# v1.net
KiCad netlist of a schematic drawn in EAGLE
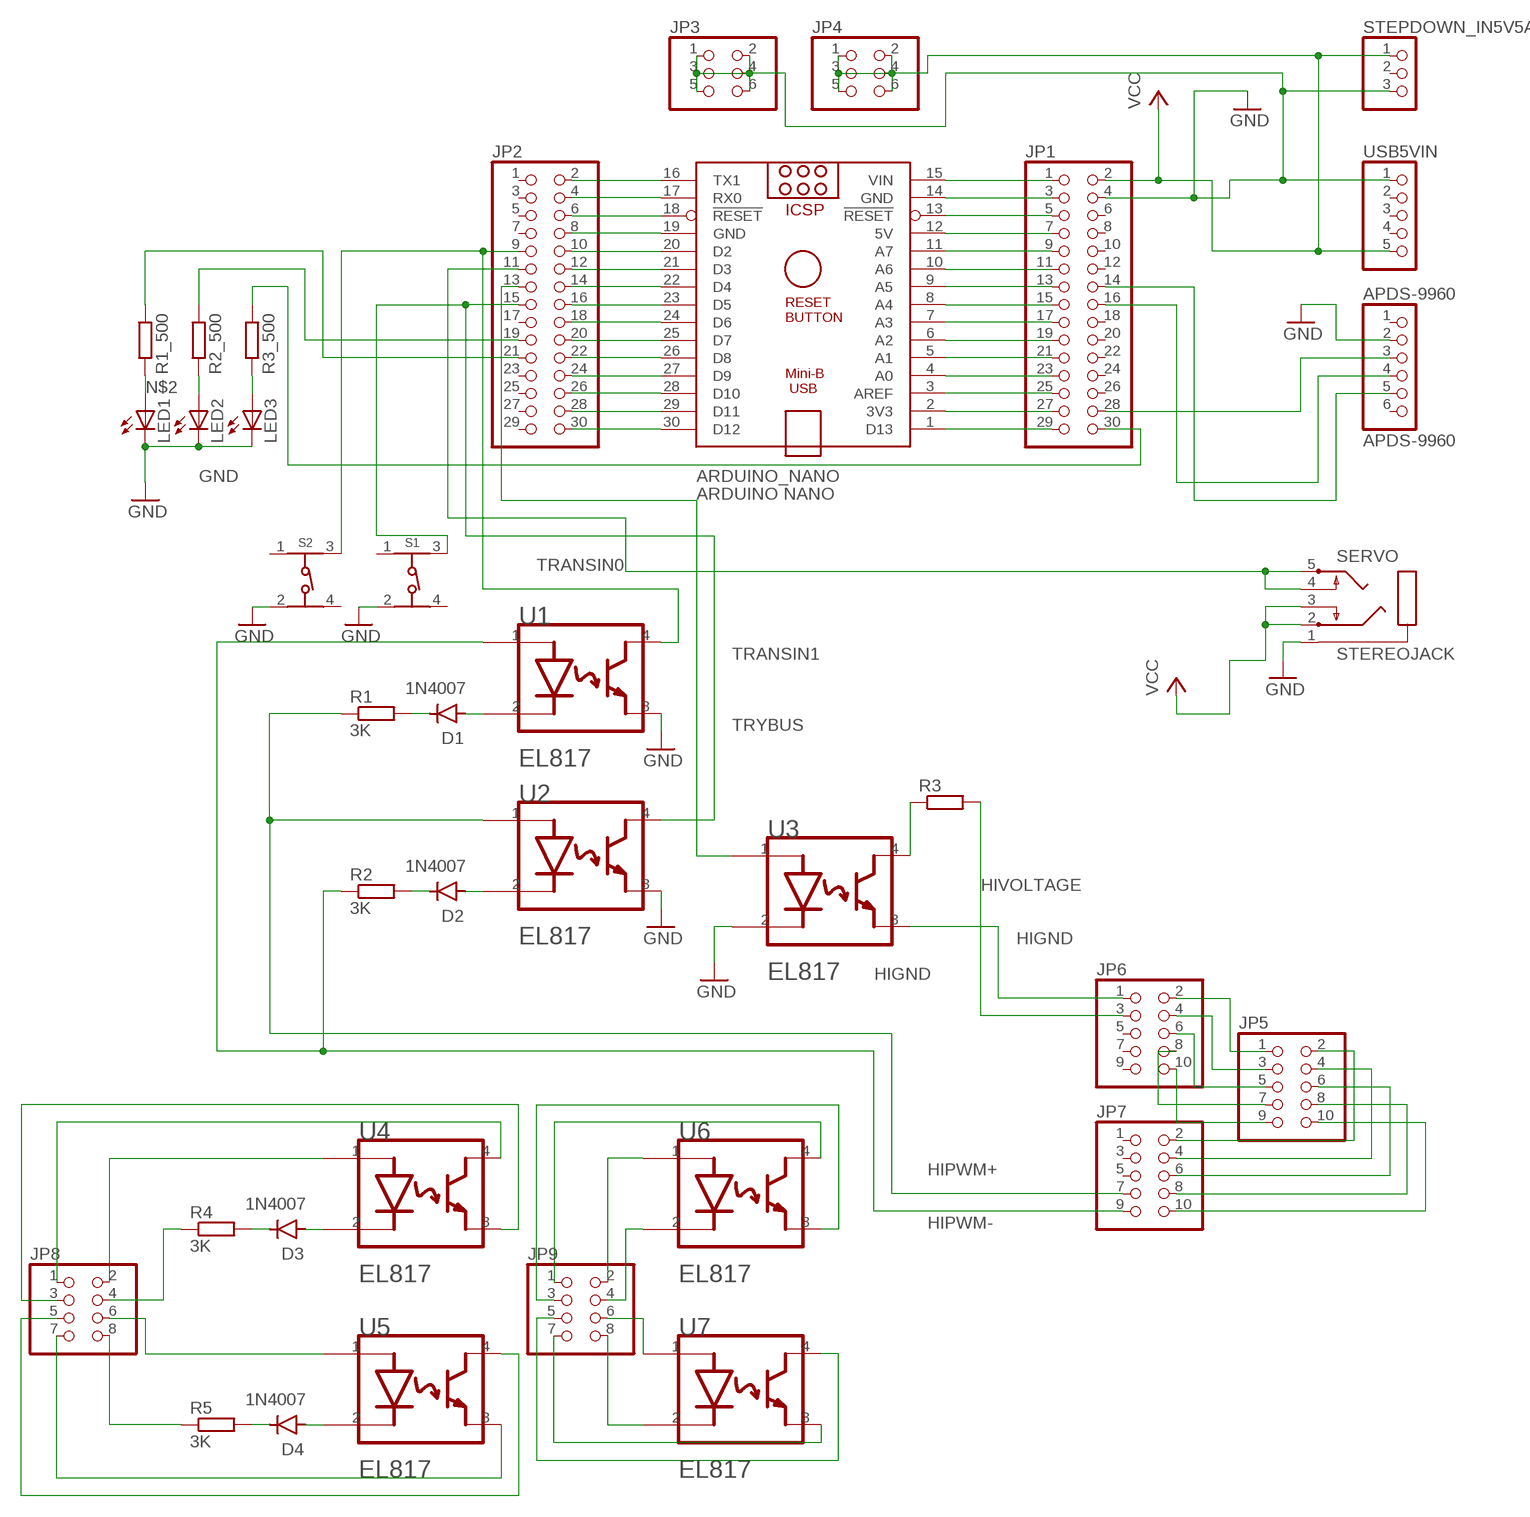
[diagram p0: schematic, sheet 1]

(export (version "E")
  (design (tool "Eeschema 10.0.6"))
  (components
    (comp (ref "APDS-9960")
      (value "APDS-9960")
      (footprint "eagle-import:1X06")
      (libsource (lib "eagle-import") (part "PINHD-1X6"))
    )
    (comp (ref "ARDUINO_NANO")
      (value "ARDUINO NANO")
      (footprint "eagle-import:ARDUINO_NANO")
      (libsource (lib "eagle-import") (part "ARDUINO_NANO"))
    )
    (comp (ref "D1")
      (value "1N4007")
      (footprint "eagle-import:DO-41")
      (fields
        (field (name "DIGIKEY_PART_NUMBER") "1N4007MSCT-ND")
        (field (name "MANUFACTURER") "Micro Commercial Co")
        (field (name "CREATED_BY") "PCBLayout.com")
      )
      (libsource (lib "eagle-import") (part "1N4007"))
    )
    (comp (ref "D2")
      (value "1N4007")
      (footprint "eagle-import:DO-41")
      (fields
        (field (name "DIGIKEY_PART_NUMBER") "1N4007MSCT-ND")
        (field (name "MANUFACTURER") "Micro Commercial Co")
        (field (name "CREATED_BY") "PCBLayout.com")
      )
      (libsource (lib "eagle-import") (part "1N4007"))
    )
    (comp (ref "D3")
      (value "1N4007")
      (footprint "eagle-import:DO-41")
      (fields
        (field (name "DIGIKEY_PART_NUMBER") "1N4007MSCT-ND")
        (field (name "MANUFACTURER") "Micro Commercial Co")
        (field (name "CREATED_BY") "PCBLayout.com")
      )
      (libsource (lib "eagle-import") (part "1N4007"))
    )
    (comp (ref "D4")
      (value "1N4007")
      (footprint "eagle-import:DO-41")
      (fields
        (field (name "DIGIKEY_PART_NUMBER") "1N4007MSCT-ND")
        (field (name "MANUFACTURER") "Micro Commercial Co")
        (field (name "CREATED_BY") "PCBLayout.com")
      )
      (libsource (lib "eagle-import") (part "1N4007"))
    )
    (comp (ref "JP1")
      (value "PINHD-2X15")
      (footprint "eagle-import:2X15")
      (libsource (lib "eagle-import") (part "PINHD-2X15"))
    )
    (comp (ref "JP2")
      (value "PINHD-2X15")
      (footprint "eagle-import:2X15")
      (libsource (lib "eagle-import") (part "PINHD-2X15"))
    )
    (comp (ref "JP3")
      (value "PINHD-2X3")
      (footprint "eagle-import:2X03")
      (libsource (lib "eagle-import") (part "PINHD-2X3"))
    )
    (comp (ref "JP4")
      (value "PINHD-2X3")
      (footprint "eagle-import:2X03")
      (libsource (lib "eagle-import") (part "PINHD-2X3"))
    )
    (comp (ref "JP5")
      (value "PINHD-2X5")
      (footprint "eagle-import:2X05")
      (libsource (lib "eagle-import") (part "PINHD-2X5"))
    )
    (comp (ref "JP6")
      (value "PINHD-2X5")
      (footprint "eagle-import:2X05")
      (libsource (lib "eagle-import") (part "PINHD-2X5"))
    )
    (comp (ref "JP7")
      (value "PINHD-2X5")
      (footprint "eagle-import:2X05")
      (libsource (lib "eagle-import") (part "PINHD-2X5"))
    )
    (comp (ref "JP8")
      (value "PINHD-2X4")
      (footprint "eagle-import:2X04")
      (libsource (lib "eagle-import") (part "PINHD-2X4"))
    )
    (comp (ref "JP9")
      (value "PINHD-2X4")
      (footprint "eagle-import:2X04")
      (libsource (lib "eagle-import") (part "PINHD-2X4"))
    )
    (comp (ref "LED1")
      (value "LED3MM")
      (footprint "eagle-import:LED3MM")
      (libsource (lib "eagle-import") (part "LED3MM"))
    )
    (comp (ref "LED2")
      (value "LED3MM")
      (footprint "eagle-import:LED3MM")
      (libsource (lib "eagle-import") (part "LED3MM"))
    )
    (comp (ref "LED3")
      (value "LED3MM")
      (footprint "eagle-import:LED3MM")
      (libsource (lib "eagle-import") (part "LED3MM"))
    )
    (comp (ref "R1")
      (value "3K")
      (footprint "eagle-import:0207_10")
      (libsource (lib "eagle-import") (part "R-EU_0207/10"))
    )
    (comp (ref "R1_500")
      (value "R-EU_0207/10")
      (footprint "eagle-import:0207_10")
      (libsource (lib "eagle-import") (part "R-EU_0207/10"))
    )
    (comp (ref "R2")
      (value "3K")
      (footprint "eagle-import:0207_10")
      (libsource (lib "eagle-import") (part "R-EU_0207/10"))
    )
    (comp (ref "R2_500")
      (value "R-EU_0207/10")
      (footprint "eagle-import:0207_10")
      (libsource (lib "eagle-import") (part "R-EU_0207/10"))
    )
    (comp (ref "R3")
      (value "R-EU_0207/10")
      (footprint "eagle-import:0207_10")
      (libsource (lib "eagle-import") (part "R-EU_0207/10"))
    )
    (comp (ref "R3_500")
      (value "R-EU_0207/10")
      (footprint "eagle-import:0207_10")
      (libsource (lib "eagle-import") (part "R-EU_0207/10"))
    )
    (comp (ref "R4")
      (value "3K")
      (footprint "eagle-import:0207_10")
      (libsource (lib "eagle-import") (part "R-EU_0207/10"))
    )
    (comp (ref "R5")
      (value "3K")
      (footprint "eagle-import:0207_10")
      (libsource (lib "eagle-import") (part "R-EU_0207/10"))
    )
    (comp (ref "S1")
      (value "430156070726")
      (footprint "eagle-import:4301X60707X6")
      (libsource (lib "eagle-import") (part "430156070726"))
    )
    (comp (ref "S2")
      (value "430156070726")
      (footprint "eagle-import:4301X60707X6")
      (libsource (lib "eagle-import") (part "430156070726"))
    )
    (comp (ref "SERVO")
      (value "STEREOJACK")
      (footprint "eagle-import:STX3100")
      (libsource (lib "eagle-import") (part "STEREOJACK"))
    )
    (comp (ref "STEPDOWN_IN5V5A")
      (value "PINHD-1X3")
      (footprint "eagle-import:1X03")
      (libsource (lib "eagle-import") (part "PINHD-1X3"))
    )
    (comp (ref "U1")
      (value "EVERLIGHT_EL817EVERLIGHT_EL817_0_0")
      (footprint "eagle-import:EVERLIGHT_EL817_0")
      (fields
        (field (name "DIGIKEY_PART_NUMBER") "EL817-ND")
        (field (name "MF") "Everlight")
        (field (name "MOUSER_PART_NUMBER") "638-817")
      )
      (libsource (lib "eagle-import") (part "EVERLIGHT_EL817EVERLIGHT_EL817_0_0"))
    )
    (comp (ref "U2")
      (value "EVERLIGHT_EL817EVERLIGHT_EL817_0_0")
      (footprint "eagle-import:EVERLIGHT_EL817_0")
      (fields
        (field (name "DIGIKEY_PART_NUMBER") "EL817-ND")
        (field (name "MF") "Everlight")
        (field (name "MOUSER_PART_NUMBER") "638-817")
      )
      (libsource (lib "eagle-import") (part "EVERLIGHT_EL817EVERLIGHT_EL817_0_0"))
    )
    (comp (ref "U3")
      (value "EVERLIGHT_EL817EVERLIGHT_EL817_0_0")
      (footprint "eagle-import:EVERLIGHT_EL817_0")
      (fields
        (field (name "DIGIKEY_PART_NUMBER") "EL817-ND")
        (field (name "MF") "Everlight")
        (field (name "MOUSER_PART_NUMBER") "638-817")
      )
      (libsource (lib "eagle-import") (part "EVERLIGHT_EL817EVERLIGHT_EL817_0_0"))
    )
    (comp (ref "U4")
      (value "EVERLIGHT_EL817EVERLIGHT_EL817_0_0")
      (footprint "eagle-import:EVERLIGHT_EL817_0")
      (fields
        (field (name "DIGIKEY_PART_NUMBER") "EL817-ND")
        (field (name "MF") "Everlight")
        (field (name "MOUSER_PART_NUMBER") "638-817")
      )
      (libsource (lib "eagle-import") (part "EVERLIGHT_EL817EVERLIGHT_EL817_0_0"))
    )
    (comp (ref "U5")
      (value "EVERLIGHT_EL817EVERLIGHT_EL817_0_0")
      (footprint "eagle-import:EVERLIGHT_EL817_0")
      (fields
        (field (name "DIGIKEY_PART_NUMBER") "EL817-ND")
        (field (name "MF") "Everlight")
        (field (name "MOUSER_PART_NUMBER") "638-817")
      )
      (libsource (lib "eagle-import") (part "EVERLIGHT_EL817EVERLIGHT_EL817_0_0"))
    )
    (comp (ref "U6")
      (value "EVERLIGHT_EL817EVERLIGHT_EL817_0_0")
      (footprint "eagle-import:EVERLIGHT_EL817_0")
      (fields
        (field (name "DIGIKEY_PART_NUMBER") "EL817-ND")
        (field (name "MF") "Everlight")
        (field (name "MOUSER_PART_NUMBER") "638-817")
      )
      (libsource (lib "eagle-import") (part "EVERLIGHT_EL817EVERLIGHT_EL817_0_0"))
    )
    (comp (ref "U7")
      (value "EVERLIGHT_EL817EVERLIGHT_EL817_0_0")
      (footprint "eagle-import:EVERLIGHT_EL817_0")
      (fields
        (field (name "DIGIKEY_PART_NUMBER") "EL817-ND")
        (field (name "MF") "Everlight")
        (field (name "MOUSER_PART_NUMBER") "638-817")
      )
      (libsource (lib "eagle-import") (part "EVERLIGHT_EL817EVERLIGHT_EL817_0_0"))
    )
    (comp (ref "USB5VIN")
      (value "PINHD-1X5")
      (footprint "eagle-import:1X05")
      (libsource (lib "eagle-import") (part "PINHD-1X5"))
    )
  )
  (nets
    (net (code "1") (name "/HIGND") (class "Default")
      (node (ref "JP6") (pin "1") (pinfunction "1_1") (pintype "passive"))
      (node (ref "U3") (pin "3") (pinfunction "EMITTER_3") (pintype "bidirectional"))
    )
    (net (code "2") (name "/HIPWM+") (class "Default")
      (node (ref "JP7") (pin "7") (pinfunction "7_7") (pintype "passive"))
      (node (ref "R1") (pin "1") (pinfunction "1_1") (pintype "passive"))
      (node (ref "U2") (pin "1") (pinfunction "ANODE_1") (pintype "bidirectional"))
    )
    (net (code "3") (name "/HIPWM-") (class "Default")
      (node (ref "JP7") (pin "9") (pinfunction "9_9") (pintype "passive"))
      (node (ref "R2") (pin "1") (pinfunction "1_1") (pintype "passive"))
      (node (ref "U1") (pin "1") (pinfunction "ANODE_1") (pintype "bidirectional"))
    )
    (net (code "4") (name "/HIVOLTAGE") (class "Default")
      (node (ref "JP6") (pin "3") (pinfunction "3_3") (pintype "passive"))
      (node (ref "R3") (pin "2") (pinfunction "2_2") (pintype "passive"))
    )
    (net (code "5") (name "/N$2") (class "Default")
      (node (ref "LED2") (pin "A") (pinfunction "A_A") (pintype "passive"))
      (node (ref "R2_500") (pin "2") (pinfunction "2_2") (pintype "passive"))
    )
    (net (code "6") (name "/TRANSIN0") (class "Default")
      (node (ref "JP2") (pin "9") (pinfunction "9_9") (pintype "passive"))
      (node (ref "S2") (pin "3") (pinfunction "3_3") (pintype "passive"))
      (node (ref "U1") (pin "4") (pinfunction "COLLECTOR_4") (pintype "bidirectional"))
    )
    (net (code "7") (name "/TRANSIN1") (class "Default")
      (node (ref "JP2") (pin "15") (pinfunction "15_15") (pintype "passive"))
      (node (ref "S1") (pin "3") (pinfunction "3_3") (pintype "passive"))
      (node (ref "U2") (pin "4") (pinfunction "COLLECTOR_4") (pintype "bidirectional"))
    )
    (net (code "8") (name "/TRYBUS") (class "Default")
      (node (ref "JP2") (pin "13") (pinfunction "13_13") (pintype "passive"))
      (node (ref "U3") (pin "1") (pinfunction "ANODE_1") (pintype "bidirectional"))
    )
    (net (code "9") (name "GND") (class "Default")
      (node (ref "APDS-9960") (pin "2") (pinfunction "2_2") (pintype "passive"))
      (node (ref "JP1") (pin "4") (pinfunction "4_4") (pintype "passive"))
      (node (ref "JP3") (pin "1") (pinfunction "1_1") (pintype "passive"))
      (node (ref "JP3") (pin "2") (pinfunction "2_2") (pintype "passive"))
      (node (ref "JP3") (pin "3") (pinfunction "3_3") (pintype "passive"))
      (node (ref "JP3") (pin "4") (pinfunction "4_4") (pintype "passive"))
      (node (ref "JP3") (pin "5") (pinfunction "5_5") (pintype "passive"))
      (node (ref "JP3") (pin "6") (pinfunction "6_6") (pintype "passive"))
      (node (ref "LED1") (pin "K") (pinfunction "C_K") (pintype "passive"))
      (node (ref "LED2") (pin "K") (pinfunction "C_K") (pintype "passive"))
      (node (ref "LED3") (pin "K") (pinfunction "C_K") (pintype "passive"))
      (node (ref "S1") (pin "2") (pinfunction "2_2") (pintype "passive"))
      (node (ref "S2") (pin "2") (pinfunction "2_2") (pintype "passive"))
      (node (ref "SERVO") (pin "1") (pinfunction "1_1") (pintype "passive"))
      (node (ref "STEPDOWN_IN5V5A") (pin "3") (pinfunction "3_3") (pintype "passive"))
      (node (ref "U1") (pin "3") (pinfunction "EMITTER_3") (pintype "bidirectional"))
      (node (ref "U2") (pin "3") (pinfunction "EMITTER_3") (pintype "bidirectional"))
      (node (ref "U3") (pin "2") (pinfunction "CATHODE_2") (pintype "bidirectional"))
      (node (ref "USB5VIN") (pin "1") (pinfunction "1_1") (pintype "passive"))
    )
    (net (code "10") (name "Net-(APDS-9960-Pad3)") (class "Default")
      (node (ref "APDS-9960") (pin "3") (pinfunction "3_3") (pintype "passive"))
      (node (ref "JP1") (pin "28") (pinfunction "28_28") (pintype "passive"))
    )
    (net (code "11") (name "Net-(APDS-9960-Pad4)") (class "Default")
      (node (ref "APDS-9960") (pin "4") (pinfunction "4_4") (pintype "passive"))
      (node (ref "JP1") (pin "16") (pinfunction "16_16") (pintype "passive"))
    )
    (net (code "12") (name "Net-(APDS-9960-Pad5)") (class "Default")
      (node (ref "APDS-9960") (pin "5") (pinfunction "5_5") (pintype "passive"))
      (node (ref "JP1") (pin "14") (pinfunction "14_14") (pintype "passive"))
    )
    (net (code "13") (name "Net-(ARDUINO_NANO-3V3)") (class "Default")
      (node (ref "ARDUINO_NANO") (pin "2") (pinfunction "3V3_2") (pintype "output"))
      (node (ref "JP1") (pin "27") (pinfunction "27_27") (pintype "passive"))
    )
    (net (code "14") (name "Net-(ARDUINO_NANO-5V)") (class "Default")
      (node (ref "ARDUINO_NANO") (pin "12") (pinfunction "5V_12") (pintype "power_in"))
      (node (ref "JP1") (pin "7") (pinfunction "7_7") (pintype "passive"))
    )
    (net (code "15") (name "Net-(ARDUINO_NANO-A0)") (class "Default")
      (node (ref "ARDUINO_NANO") (pin "4") (pinfunction "A0_4") (pintype "bidirectional"))
      (node (ref "JP1") (pin "23") (pinfunction "23_23") (pintype "passive"))
    )
    (net (code "16") (name "Net-(ARDUINO_NANO-A1)") (class "Default")
      (node (ref "ARDUINO_NANO") (pin "5") (pinfunction "A1_5") (pintype "bidirectional"))
      (node (ref "JP1") (pin "21") (pinfunction "21_21") (pintype "passive"))
    )
    (net (code "17") (name "Net-(ARDUINO_NANO-A2)") (class "Default")
      (node (ref "ARDUINO_NANO") (pin "6") (pinfunction "A2_6") (pintype "bidirectional"))
      (node (ref "JP1") (pin "19") (pinfunction "19_19") (pintype "passive"))
    )
    (net (code "18") (name "Net-(ARDUINO_NANO-A3)") (class "Default")
      (node (ref "ARDUINO_NANO") (pin "7") (pinfunction "A3_7") (pintype "bidirectional"))
      (node (ref "JP1") (pin "17") (pinfunction "17_17") (pintype "passive"))
    )
    (net (code "19") (name "Net-(ARDUINO_NANO-A4)") (class "Default")
      (node (ref "ARDUINO_NANO") (pin "8") (pinfunction "A4_8") (pintype "bidirectional"))
      (node (ref "JP1") (pin "15") (pinfunction "15_15") (pintype "passive"))
    )
    (net (code "20") (name "Net-(ARDUINO_NANO-A5)") (class "Default")
      (node (ref "ARDUINO_NANO") (pin "9") (pinfunction "A5_9") (pintype "bidirectional"))
      (node (ref "JP1") (pin "13") (pinfunction "13_13") (pintype "passive"))
    )
    (net (code "21") (name "Net-(ARDUINO_NANO-A6)") (class "Default")
      (node (ref "ARDUINO_NANO") (pin "10") (pinfunction "A6_10") (pintype "bidirectional"))
      (node (ref "JP1") (pin "11") (pinfunction "11_11") (pintype "passive"))
    )
    (net (code "22") (name "Net-(ARDUINO_NANO-A7)") (class "Default")
      (node (ref "ARDUINO_NANO") (pin "11") (pinfunction "A7_11") (pintype "bidirectional"))
      (node (ref "JP1") (pin "9") (pinfunction "9_9") (pintype "passive"))
    )
    (net (code "23") (name "Net-(ARDUINO_NANO-AREF)") (class "Default")
      (node (ref "ARDUINO_NANO") (pin "3") (pinfunction "AREF_3") (pintype "input"))
      (node (ref "JP1") (pin "25") (pinfunction "25_25") (pintype "passive"))
    )
    (net (code "24") (name "Net-(ARDUINO_NANO-D2)") (class "Default")
      (node (ref "ARDUINO_NANO") (pin "20") (pinfunction "D2_20") (pintype "bidirectional"))
      (node (ref "JP2") (pin "10") (pinfunction "10_10") (pintype "passive"))
    )
    (net (code "25") (name "Net-(ARDUINO_NANO-D3)") (class "Default")
      (node (ref "ARDUINO_NANO") (pin "21") (pinfunction "D3_21") (pintype "bidirectional"))
      (node (ref "JP2") (pin "12") (pinfunction "12_12") (pintype "passive"))
    )
    (net (code "26") (name "Net-(ARDUINO_NANO-D4)") (class "Default")
      (node (ref "ARDUINO_NANO") (pin "22") (pinfunction "D4_22") (pintype "bidirectional"))
      (node (ref "JP2") (pin "14") (pinfunction "14_14") (pintype "passive"))
    )
    (net (code "27") (name "Net-(ARDUINO_NANO-D5)") (class "Default")
      (node (ref "ARDUINO_NANO") (pin "23") (pinfunction "D5_23") (pintype "bidirectional"))
      (node (ref "JP2") (pin "16") (pinfunction "16_16") (pintype "passive"))
    )
    (net (code "28") (name "Net-(ARDUINO_NANO-D6)") (class "Default")
      (node (ref "ARDUINO_NANO") (pin "24") (pinfunction "D6_24") (pintype "bidirectional"))
      (node (ref "JP2") (pin "18") (pinfunction "18_18") (pintype "passive"))
    )
    (net (code "29") (name "Net-(ARDUINO_NANO-D7)") (class "Default")
      (node (ref "ARDUINO_NANO") (pin "25") (pinfunction "D7_25") (pintype "bidirectional"))
      (node (ref "JP2") (pin "20") (pinfunction "20_20") (pintype "passive"))
    )
    (net (code "30") (name "Net-(ARDUINO_NANO-D8)") (class "Default")
      (node (ref "ARDUINO_NANO") (pin "26") (pinfunction "D8_26") (pintype "bidirectional"))
      (node (ref "JP2") (pin "22") (pinfunction "22_22") (pintype "passive"))
    )
    (net (code "31") (name "Net-(ARDUINO_NANO-D9)") (class "Default")
      (node (ref "ARDUINO_NANO") (pin "27") (pinfunction "D9_27") (pintype "bidirectional"))
      (node (ref "JP2") (pin "24") (pinfunction "24_24") (pintype "passive"))
    )
    (net (code "32") (name "Net-(ARDUINO_NANO-D10)") (class "Default")
      (node (ref "ARDUINO_NANO") (pin "28") (pinfunction "D10_28") (pintype "bidirectional"))
      (node (ref "JP2") (pin "26") (pinfunction "26_26") (pintype "passive"))
    )
    (net (code "33") (name "Net-(ARDUINO_NANO-D11)") (class "Default")
      (node (ref "ARDUINO_NANO") (pin "29") (pinfunction "D11_29") (pintype "bidirectional"))
      (node (ref "JP2") (pin "28") (pinfunction "28_28") (pintype "passive"))
    )
    (net (code "34") (name "Net-(ARDUINO_NANO-D12)") (class "Default")
      (node (ref "ARDUINO_NANO") (pin "30") (pinfunction "D12_30") (pintype "bidirectional"))
      (node (ref "JP2") (pin "30") (pinfunction "30_30") (pintype "passive"))
    )
    (net (code "35") (name "Net-(ARDUINO_NANO-D13)") (class "Default")
      (node (ref "ARDUINO_NANO") (pin "1") (pinfunction "D13_1") (pintype "bidirectional"))
      (node (ref "JP1") (pin "29") (pinfunction "29_29") (pintype "passive"))
    )
    (net (code "36") (name "Net-(ARDUINO_NANO-GND-Pad14)") (class "Default")
      (node (ref "ARDUINO_NANO") (pin "14") (pinfunction "GND_14") (pintype "power_in"))
      (node (ref "JP1") (pin "3") (pinfunction "3_3") (pintype "passive"))
    )
    (net (code "37") (name "Net-(ARDUINO_NANO-GND-Pad19)") (class "Default")
      (node (ref "ARDUINO_NANO") (pin "19") (pinfunction "GND_19") (pintype "power_in"))
      (node (ref "JP2") (pin "8") (pinfunction "8_8") (pintype "passive"))
    )
    (net (code "38") (name "Net-(ARDUINO_NANO-RX0)") (class "Default")
      (node (ref "ARDUINO_NANO") (pin "17") (pinfunction "RX0_17") (pintype "bidirectional"))
      (node (ref "JP2") (pin "4") (pinfunction "4_4") (pintype "passive"))
    )
    (net (code "39") (name "Net-(ARDUINO_NANO-TX1)") (class "Default")
      (node (ref "ARDUINO_NANO") (pin "16") (pinfunction "TX1_16") (pintype "bidirectional"))
      (node (ref "JP2") (pin "2") (pinfunction "2_2") (pintype "passive"))
    )
    (net (code "40") (name "Net-(ARDUINO_NANO-VIN)") (class "Default")
      (node (ref "ARDUINO_NANO") (pin "15") (pinfunction "VIN_15") (pintype "power_in"))
      (node (ref "JP1") (pin "1") (pinfunction "1_1") (pintype "passive"))
    )
    (net (code "41") (name "Net-(ARDUINO_NANO-~{RESET}-Pad13)") (class "Default")
      (node (ref "ARDUINO_NANO") (pin "13") (pinfunction "~{RESET}_13") (pintype "input"))
      (node (ref "JP1") (pin "5") (pinfunction "5_5") (pintype "passive"))
    )
    (net (code "42") (name "Net-(ARDUINO_NANO-~{RESET}-Pad18)") (class "Default")
      (node (ref "ARDUINO_NANO") (pin "18") (pinfunction "~{RESET}_18") (pintype "input"))
      (node (ref "JP2") (pin "6") (pinfunction "6_6") (pintype "passive"))
    )
    (net (code "43") (name "Net-(D1-PadC)") (class "Default")
      (node (ref "D1") (pin "C") (pinfunction "C_C") (pintype "passive"))
      (node (ref "R1") (pin "2") (pinfunction "2_2") (pintype "passive"))
    )
    (net (code "44") (name "Net-(D2-PadC)") (class "Default")
      (node (ref "D2") (pin "C") (pinfunction "C_C") (pintype "passive"))
      (node (ref "R2") (pin "2") (pinfunction "2_2") (pintype "passive"))
    )
    (net (code "45") (name "Net-(D3-PadC)") (class "Default")
      (node (ref "D3") (pin "C") (pinfunction "C_C") (pintype "passive"))
      (node (ref "R4") (pin "2") (pinfunction "2_2") (pintype "passive"))
    )
    (net (code "46") (name "Net-(D4-PadC)") (class "Default")
      (node (ref "D4") (pin "C") (pinfunction "C_C") (pintype "passive"))
      (node (ref "R5") (pin "2") (pinfunction "2_2") (pintype "passive"))
    )
    (net (code "47") (name "Net-(JP1-Pad30)") (class "Default")
      (node (ref "JP1") (pin "30") (pinfunction "30_30") (pintype "passive"))
      (node (ref "R3_500") (pin "1") (pinfunction "1_1") (pintype "passive"))
    )
    (net (code "48") (name "Net-(JP2-Pad11)") (class "Default")
      (node (ref "JP2") (pin "11") (pinfunction "11_11") (pintype "passive"))
      (node (ref "SERVO") (pin "4") (pinfunction "4_4") (pintype "passive"))
      (node (ref "SERVO") (pin "5") (pinfunction "5_5") (pintype "passive"))
    )
    (net (code "49") (name "Net-(JP2-Pad19)") (class "Default")
      (node (ref "JP2") (pin "19") (pinfunction "19_19") (pintype "passive"))
      (node (ref "R2_500") (pin "1") (pinfunction "1_1") (pintype "passive"))
    )
    (net (code "50") (name "Net-(JP2-Pad21)") (class "Default")
      (node (ref "JP2") (pin "21") (pinfunction "21_21") (pintype "passive"))
      (node (ref "R1_500") (pin "1") (pinfunction "1_1") (pintype "passive"))
    )
    (net (code "51") (name "Net-(JP5-Pad1)") (class "Default")
      (node (ref "JP5") (pin "1") (pinfunction "1_1") (pintype "passive"))
      (node (ref "JP6") (pin "2") (pinfunction "2_2") (pintype "passive"))
    )
    (net (code "52") (name "Net-(JP5-Pad2)") (class "Default")
      (node (ref "JP5") (pin "2") (pinfunction "2_2") (pintype "passive"))
      (node (ref "JP7") (pin "2") (pinfunction "2_2") (pintype "passive"))
    )
    (net (code "53") (name "Net-(JP5-Pad3)") (class "Default")
      (node (ref "JP5") (pin "3") (pinfunction "3_3") (pintype "passive"))
      (node (ref "JP6") (pin "4") (pinfunction "4_4") (pintype "passive"))
    )
    (net (code "54") (name "Net-(JP5-Pad4)") (class "Default")
      (node (ref "JP5") (pin "4") (pinfunction "4_4") (pintype "passive"))
      (node (ref "JP7") (pin "4") (pinfunction "4_4") (pintype "passive"))
    )
    (net (code "55") (name "Net-(JP5-Pad5)") (class "Default")
      (node (ref "JP5") (pin "5") (pinfunction "5_5") (pintype "passive"))
      (node (ref "JP6") (pin "6") (pinfunction "6_6") (pintype "passive"))
    )
    (net (code "56") (name "Net-(JP5-Pad6)") (class "Default")
      (node (ref "JP5") (pin "6") (pinfunction "6_6") (pintype "passive"))
      (node (ref "JP7") (pin "6") (pinfunction "6_6") (pintype "passive"))
    )
    (net (code "57") (name "Net-(JP5-Pad7)") (class "Default")
      (node (ref "JP5") (pin "7") (pinfunction "7_7") (pintype "passive"))
      (node (ref "JP6") (pin "8") (pinfunction "8_8") (pintype "passive"))
    )
    (net (code "58") (name "Net-(JP5-Pad8)") (class "Default")
      (node (ref "JP5") (pin "8") (pinfunction "8_8") (pintype "passive"))
      (node (ref "JP7") (pin "8") (pinfunction "8_8") (pintype "passive"))
    )
    (net (code "59") (name "Net-(JP5-Pad9)") (class "Default")
      (node (ref "JP5") (pin "9") (pinfunction "9_9") (pintype "passive"))
      (node (ref "JP6") (pin "10") (pinfunction "10_10") (pintype "passive"))
    )
    (net (code "60") (name "Net-(JP5-Pad10)") (class "Default")
      (node (ref "JP5") (pin "10") (pinfunction "10_10") (pintype "passive"))
      (node (ref "JP7") (pin "10") (pinfunction "10_10") (pintype "passive"))
    )
    (net (code "61") (name "Net-(JP8-Pad4)") (class "Default")
      (node (ref "JP8") (pin "4") (pinfunction "4_4") (pintype "passive"))
      (node (ref "R4") (pin "1") (pinfunction "1_1") (pintype "passive"))
    )
    (net (code "62") (name "Net-(JP8-Pad8)") (class "Default")
      (node (ref "JP8") (pin "8") (pinfunction "8_8") (pintype "passive"))
      (node (ref "R5") (pin "1") (pinfunction "1_1") (pintype "passive"))
    )
    (net (code "63") (name "Net-(LED1-PadA)") (class "Default")
      (node (ref "LED1") (pin "A") (pinfunction "A_A") (pintype "passive"))
      (node (ref "R1_500") (pin "2") (pinfunction "2_2") (pintype "passive"))
    )
    (net (code "64") (name "Net-(LED3-PadA)") (class "Default")
      (node (ref "LED3") (pin "A") (pinfunction "A_A") (pintype "passive"))
      (node (ref "R3_500") (pin "2") (pinfunction "2_2") (pintype "passive"))
    )
    (net (code "65") (name "Net-(U1-CATHODE)") (class "Default")
      (node (ref "D1") (pin "A") (pinfunction "A_A") (pintype "passive"))
      (node (ref "U1") (pin "2") (pinfunction "CATHODE_2") (pintype "bidirectional"))
    )
    (net (code "66") (name "Net-(U2-CATHODE)") (class "Default")
      (node (ref "D2") (pin "A") (pinfunction "A_A") (pintype "passive"))
      (node (ref "U2") (pin "2") (pinfunction "CATHODE_2") (pintype "bidirectional"))
    )
    (net (code "67") (name "Net-(U3-COLLECTOR)") (class "Default")
      (node (ref "R3") (pin "1") (pinfunction "1_1") (pintype "passive"))
      (node (ref "U3") (pin "4") (pinfunction "COLLECTOR_4") (pintype "bidirectional"))
    )
    (net (code "68") (name "Net-(U4-ANODE)") (class "Default")
      (node (ref "JP8") (pin "2") (pinfunction "2_2") (pintype "passive"))
      (node (ref "U4") (pin "1") (pinfunction "ANODE_1") (pintype "bidirectional"))
    )
    (net (code "69") (name "Net-(U4-CATHODE)") (class "Default")
      (node (ref "D3") (pin "A") (pinfunction "A_A") (pintype "passive"))
      (node (ref "U4") (pin "2") (pinfunction "CATHODE_2") (pintype "bidirectional"))
    )
    (net (code "70") (name "Net-(U4-COLLECTOR)") (class "Default")
      (node (ref "JP8") (pin "1") (pinfunction "1_1") (pintype "passive"))
      (node (ref "U4") (pin "4") (pinfunction "COLLECTOR_4") (pintype "bidirectional"))
    )
    (net (code "71") (name "Net-(U4-EMITTER)") (class "Default")
      (node (ref "JP8") (pin "3") (pinfunction "3_3") (pintype "passive"))
      (node (ref "U4") (pin "3") (pinfunction "EMITTER_3") (pintype "bidirectional"))
    )
    (net (code "72") (name "Net-(U5-ANODE)") (class "Default")
      (node (ref "JP8") (pin "6") (pinfunction "6_6") (pintype "passive"))
      (node (ref "U5") (pin "1") (pinfunction "ANODE_1") (pintype "bidirectional"))
    )
    (net (code "73") (name "Net-(U5-CATHODE)") (class "Default")
      (node (ref "D4") (pin "A") (pinfunction "A_A") (pintype "passive"))
      (node (ref "U5") (pin "2") (pinfunction "CATHODE_2") (pintype "bidirectional"))
    )
    (net (code "74") (name "Net-(U5-COLLECTOR)") (class "Default")
      (node (ref "JP8") (pin "5") (pinfunction "5_5") (pintype "passive"))
      (node (ref "U5") (pin "4") (pinfunction "COLLECTOR_4") (pintype "bidirectional"))
    )
    (net (code "75") (name "Net-(U5-EMITTER)") (class "Default")
      (node (ref "JP8") (pin "7") (pinfunction "7_7") (pintype "passive"))
      (node (ref "U5") (pin "3") (pinfunction "EMITTER_3") (pintype "bidirectional"))
    )
    (net (code "76") (name "Net-(U6-ANODE)") (class "Default")
      (node (ref "JP9") (pin "2") (pinfunction "2_2") (pintype "passive"))
      (node (ref "U6") (pin "1") (pinfunction "ANODE_1") (pintype "bidirectional"))
    )
    (net (code "77") (name "Net-(U6-CATHODE)") (class "Default")
      (node (ref "JP9") (pin "4") (pinfunction "4_4") (pintype "passive"))
      (node (ref "U6") (pin "2") (pinfunction "CATHODE_2") (pintype "bidirectional"))
    )
    (net (code "78") (name "Net-(U6-COLLECTOR)") (class "Default")
      (node (ref "JP9") (pin "1") (pinfunction "1_1") (pintype "passive"))
      (node (ref "U6") (pin "4") (pinfunction "COLLECTOR_4") (pintype "bidirectional"))
    )
    (net (code "79") (name "Net-(U6-EMITTER)") (class "Default")
      (node (ref "JP9") (pin "3") (pinfunction "3_3") (pintype "passive"))
      (node (ref "U6") (pin "3") (pinfunction "EMITTER_3") (pintype "bidirectional"))
    )
    (net (code "80") (name "Net-(U7-ANODE)") (class "Default")
      (node (ref "JP9") (pin "6") (pinfunction "6_6") (pintype "passive"))
      (node (ref "U7") (pin "1") (pinfunction "ANODE_1") (pintype "bidirectional"))
    )
    (net (code "81") (name "Net-(U7-CATHODE)") (class "Default")
      (node (ref "JP9") (pin "8") (pinfunction "8_8") (pintype "passive"))
      (node (ref "U7") (pin "2") (pinfunction "CATHODE_2") (pintype "bidirectional"))
    )
    (net (code "82") (name "Net-(U7-COLLECTOR)") (class "Default")
      (node (ref "JP9") (pin "5") (pinfunction "5_5") (pintype "passive"))
      (node (ref "U7") (pin "4") (pinfunction "COLLECTOR_4") (pintype "bidirectional"))
    )
    (net (code "83") (name "Net-(U7-EMITTER)") (class "Default")
      (node (ref "JP9") (pin "7") (pinfunction "7_7") (pintype "passive"))
      (node (ref "U7") (pin "3") (pinfunction "EMITTER_3") (pintype "bidirectional"))
    )
    (net (code "84") (name "VCC") (class "Default")
      (node (ref "JP1") (pin "2") (pinfunction "2_2") (pintype "passive"))
      (node (ref "JP4") (pin "1") (pinfunction "1_1") (pintype "passive"))
      (node (ref "JP4") (pin "2") (pinfunction "2_2") (pintype "passive"))
      (node (ref "JP4") (pin "3") (pinfunction "3_3") (pintype "passive"))
      (node (ref "JP4") (pin "4") (pinfunction "4_4") (pintype "passive"))
      (node (ref "JP4") (pin "5") (pinfunction "5_5") (pintype "passive"))
      (node (ref "JP4") (pin "6") (pinfunction "6_6") (pintype "passive"))
      (node (ref "SERVO") (pin "2") (pinfunction "2_2") (pintype "passive"))
      (node (ref "SERVO") (pin "3") (pinfunction "3_3") (pintype "passive"))
      (node (ref "STEPDOWN_IN5V5A") (pin "1") (pinfunction "1_1") (pintype "passive"))
      (node (ref "USB5VIN") (pin "5") (pinfunction "5_5") (pintype "passive"))
    )
    (net (code "85") (name "unconnected-(APDS-9960-Pad1)") (class "Default")
      (node (ref "APDS-9960") (pin "1") (pinfunction "1_1") (pintype "passive"))
    )
    (net (code "86") (name "unconnected-(APDS-9960-Pad6)") (class "Default")
      (node (ref "APDS-9960") (pin "6") (pinfunction "6_6") (pintype "passive"))
    )
    (net (code "87") (name "unconnected-(JP1-Pad6)") (class "Default")
      (node (ref "JP1") (pin "6") (pinfunction "6_6") (pintype "passive"))
    )
    (net (code "88") (name "unconnected-(JP1-Pad8)") (class "Default")
      (node (ref "JP1") (pin "8") (pinfunction "8_8") (pintype "passive"))
    )
    (net (code "89") (name "unconnected-(JP1-Pad10)") (class "Default")
      (node (ref "JP1") (pin "10") (pinfunction "10_10") (pintype "passive"))
    )
    (net (code "90") (name "unconnected-(JP1-Pad12)") (class "Default")
      (node (ref "JP1") (pin "12") (pinfunction "12_12") (pintype "passive"))
    )
    (net (code "91") (name "unconnected-(JP1-Pad18)") (class "Default")
      (node (ref "JP1") (pin "18") (pinfunction "18_18") (pintype "passive"))
    )
    (net (code "92") (name "unconnected-(JP1-Pad20)") (class "Default")
      (node (ref "JP1") (pin "20") (pinfunction "20_20") (pintype "passive"))
    )
    (net (code "93") (name "unconnected-(JP1-Pad22)") (class "Default")
      (node (ref "JP1") (pin "22") (pinfunction "22_22") (pintype "passive"))
    )
    (net (code "94") (name "unconnected-(JP1-Pad24)") (class "Default")
      (node (ref "JP1") (pin "24") (pinfunction "24_24") (pintype "passive"))
    )
    (net (code "95") (name "unconnected-(JP1-Pad26)") (class "Default")
      (node (ref "JP1") (pin "26") (pinfunction "26_26") (pintype "passive"))
    )
    (net (code "96") (name "unconnected-(JP2-Pad1)") (class "Default")
      (node (ref "JP2") (pin "1") (pinfunction "1_1") (pintype "passive"))
    )
    (net (code "97") (name "unconnected-(JP2-Pad3)") (class "Default")
      (node (ref "JP2") (pin "3") (pinfunction "3_3") (pintype "passive"))
    )
    (net (code "98") (name "unconnected-(JP2-Pad5)") (class "Default")
      (node (ref "JP2") (pin "5") (pinfunction "5_5") (pintype "passive"))
    )
    (net (code "99") (name "unconnected-(JP2-Pad7)") (class "Default")
      (node (ref "JP2") (pin "7") (pinfunction "7_7") (pintype "passive"))
    )
    (net (code "100") (name "unconnected-(JP2-Pad17)") (class "Default")
      (node (ref "JP2") (pin "17") (pinfunction "17_17") (pintype "passive"))
    )
    (net (code "101") (name "unconnected-(JP2-Pad23)") (class "Default")
      (node (ref "JP2") (pin "23") (pinfunction "23_23") (pintype "passive"))
    )
    (net (code "102") (name "unconnected-(JP2-Pad25)") (class "Default")
      (node (ref "JP2") (pin "25") (pinfunction "25_25") (pintype "passive"))
    )
    (net (code "103") (name "unconnected-(JP2-Pad27)") (class "Default")
      (node (ref "JP2") (pin "27") (pinfunction "27_27") (pintype "passive"))
    )
    (net (code "104") (name "unconnected-(JP2-Pad29)") (class "Default")
      (node (ref "JP2") (pin "29") (pinfunction "29_29") (pintype "passive"))
    )
    (net (code "105") (name "unconnected-(JP6-Pad5)") (class "Default")
      (node (ref "JP6") (pin "5") (pinfunction "5_5") (pintype "passive"))
    )
    (net (code "106") (name "unconnected-(JP6-Pad7)") (class "Default")
      (node (ref "JP6") (pin "7") (pinfunction "7_7") (pintype "passive"))
    )
    (net (code "107") (name "unconnected-(JP6-Pad9)") (class "Default")
      (node (ref "JP6") (pin "9") (pinfunction "9_9") (pintype "passive"))
    )
    (net (code "108") (name "unconnected-(JP7-Pad1)") (class "Default")
      (node (ref "JP7") (pin "1") (pinfunction "1_1") (pintype "passive"))
    )
    (net (code "109") (name "unconnected-(JP7-Pad3)") (class "Default")
      (node (ref "JP7") (pin "3") (pinfunction "3_3") (pintype "passive"))
    )
    (net (code "110") (name "unconnected-(JP7-Pad5)") (class "Default")
      (node (ref "JP7") (pin "5") (pinfunction "5_5") (pintype "passive"))
    )
    (net (code "111") (name "unconnected-(S1-Pad1)") (class "Default")
      (node (ref "S1") (pin "1") (pinfunction "1_1") (pintype "passive"))
    )
    (net (code "112") (name "unconnected-(S1-Pad4)") (class "Default")
      (node (ref "S1") (pin "4") (pinfunction "4_4") (pintype "passive"))
    )
    (net (code "113") (name "unconnected-(S2-Pad1)") (class "Default")
      (node (ref "S2") (pin "1") (pinfunction "1_1") (pintype "passive"))
    )
    (net (code "114") (name "unconnected-(S2-Pad4)") (class "Default")
      (node (ref "S2") (pin "4") (pinfunction "4_4") (pintype "passive"))
    )
    (net (code "115") (name "unconnected-(STEPDOWN_IN5V5A-Pad2)") (class "Default")
      (node (ref "STEPDOWN_IN5V5A") (pin "2") (pinfunction "2_2") (pintype "passive"))
    )
    (net (code "116") (name "unconnected-(USB5VIN-Pad2)") (class "Default")
      (node (ref "USB5VIN") (pin "2") (pinfunction "2_2") (pintype "passive"))
    )
    (net (code "117") (name "unconnected-(USB5VIN-Pad3)") (class "Default")
      (node (ref "USB5VIN") (pin "3") (pinfunction "3_3") (pintype "passive"))
    )
    (net (code "118") (name "unconnected-(USB5VIN-Pad4)") (class "Default")
      (node (ref "USB5VIN") (pin "4") (pinfunction "4_4") (pintype "passive"))
    )
  )
)
